# Power_Supply.net
KiCad netlist of a schematic drawn in Altium Designer
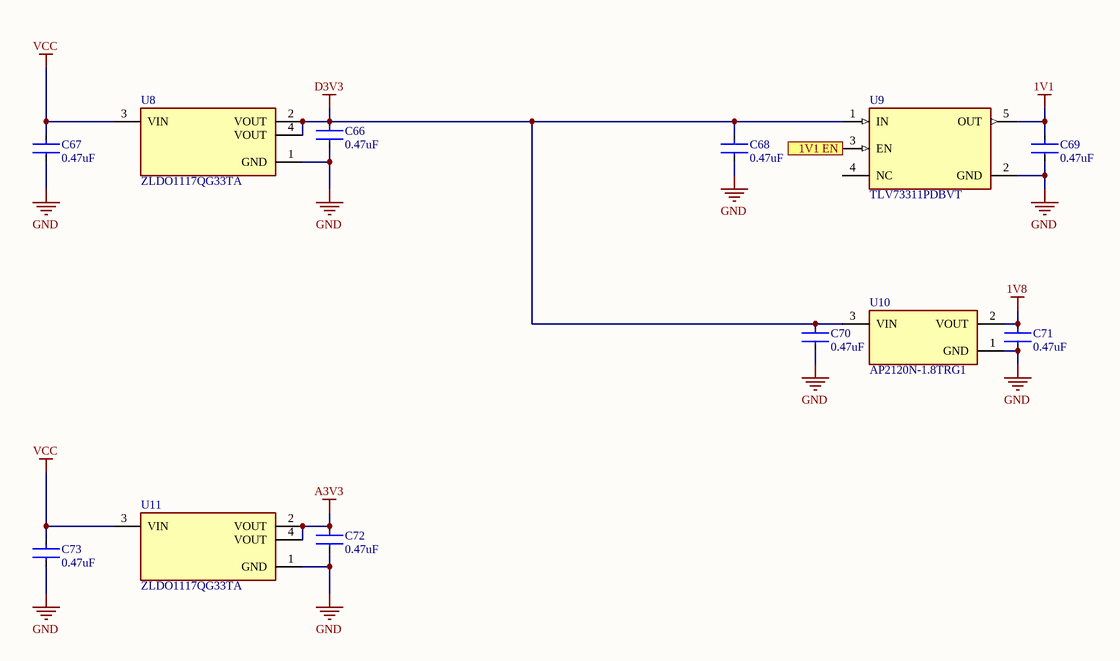
[diagram p0: Power Supply.SchDoc]

(export (version "E")
  (design (tool "Eeschema 10.0.6"))
  (components
    (comp (ref "C66")
      (value "0.47uF")
      (footprint "FP-GRM15-MFG")
      (description "CAP CER 0.1UF 16V X7R 0402")
      (fields (field (name "MANUFACTURER PART NUMBER") "GRM155R71C104KA88D") (field (name "TOLERANCE") "10%"))
      (libsource (lib "Altium Content Vault") (part "236180d848d6139a670b325ea6854c9"))
    )
    (comp (ref "C67")
      (value "0.47uF")
      (footprint "FP-GRM15-MFG")
      (description "CAP CER 0.1UF 16V X7R 0402")
      (fields (field (name "MANUFACTURER PART NUMBER") "GRM155R71C104KA88D") (field (name "TOLERANCE") "10%"))
      (libsource (lib "Altium Content Vault") (part "236180d848d6139a670b325ea6854c9"))
    )
    (comp (ref "C68")
      (value "0.47uF")
      (footprint "FP-GRM15-MFG")
      (description "CAP CER 0.1UF 16V X7R 0402")
      (fields (field (name "MANUFACTURER PART NUMBER") "GRM155R71C104KA88D") (field (name "TOLERANCE") "10%"))
      (libsource (lib "Altium Content Vault") (part "236180d848d6139a670b325ea6854c9"))
    )
    (comp (ref "C69")
      (value "0.47uF")
      (footprint "FP-GRM15-MFG")
      (description "CAP CER 0.1UF 16V X7R 0402")
      (fields (field (name "MANUFACTURER PART NUMBER") "GRM155R71C104KA88D") (field (name "TOLERANCE") "10%"))
      (libsource (lib "Altium Content Vault") (part "236180d848d6139a670b325ea6854c9"))
    )
    (comp (ref "C70")
      (value "0.47uF")
      (footprint "FP-GRM15-MFG")
      (description "CAP CER 0.1UF 16V X7R 0402")
      (fields (field (name "MANUFACTURER PART NUMBER") "GRM155R71C104KA88D") (field (name "TOLERANCE") "10%"))
      (libsource (lib "Altium Content Vault") (part "236180d848d6139a670b325ea6854c9"))
    )
    (comp (ref "C71")
      (value "0.47uF")
      (footprint "FP-GRM15-MFG")
      (description "CAP CER 0.1UF 16V X7R 0402")
      (fields (field (name "MANUFACTURER PART NUMBER") "GRM155R71C104KA88D") (field (name "TOLERANCE") "10%"))
      (libsource (lib "Altium Content Vault") (part "236180d848d6139a670b325ea6854c9"))
    )
    (comp (ref "C72")
      (value "0.47uF")
      (footprint "FP-GRM15-MFG")
      (description "CAP CER 0.1UF 16V X7R 0402")
      (fields (field (name "MANUFACTURER PART NUMBER") "GRM155R71C104KA88D") (field (name "TOLERANCE") "10%"))
      (libsource (lib "Altium Content Vault") (part "236180d848d6139a670b325ea6854c9"))
    )
    (comp (ref "C73")
      (value "0.47uF")
      (footprint "FP-GRM15-MFG")
      (description "CAP CER 0.1UF 16V X7R 0402")
      (fields (field (name "MANUFACTURER PART NUMBER") "GRM155R71C104KA88D") (field (name "TOLERANCE") "10%"))
      (libsource (lib "Altium Content Vault") (part "236180d848d6139a670b325ea6854c9"))
    )
    (comp (ref "U8")
      (value "ZLDO1117QG33TA")
      (footprint "FP-SOT223-MFG")
      (description "IC REG LINEAR 3.3V 1A SOT223-3")
      (fields (field (name "TOLERANCE") "2%"))
      (libsource (lib "Altium Content Vault") (part "e8e3cda12977690329f4a6520c2f0b2"))
    )
    (comp (ref "U9")
      (value "TLV73311PDBVT")
      (footprint "FP-DBV0005A-IPC_C")
      (description "IC REG LINEAR 1.1V 300MA SOT23-5")
      (libsource (lib "Altium Content Vault") (part "4670bf8a164e1b8604192632250c220"))
    )
    (comp (ref "U10")
      (value "AP2120N-1.8TRG1")
      (footprint "FP-SOT23-IPC_A")
      (description "IC REG LINEAR 1.8V 150MA SOT23")
      (libsource (lib "Altium Content Vault") (part "99960f24aedc7394e144d1df79132fe"))
    )
    (comp (ref "U11")
      (value "ZLDO1117QG33TA")
      (footprint "FP-SOT223-MFG")
      (description "IC REG LINEAR 3.3V 1A SOT223-3")
      (fields (field (name "TOLERANCE") "2%"))
      (libsource (lib "Altium Content Vault") (part "e8e3cda12977690329f4a6520c2f0b2"))
    )
  )
  (nets
    (net (code "1") (name "/1V1 EN") (class "Default")
      (node (ref "U9") (pin "3") (pinfunction "EN_3") (pintype "input"))
    )
    (net (code "2") (name "1V1") (class "Default")
      (node (ref "C69") (pin "2") (pinfunction "2_2") (pintype "passive"))
      (node (ref "U9") (pin "5") (pinfunction "OUT_5") (pintype "output"))
    )
    (net (code "3") (name "1V8") (class "Default")
      (node (ref "C71") (pin "2") (pinfunction "2_2") (pintype "passive"))
      (node (ref "U10") (pin "2") (pinfunction "VOUT_2") (pintype "power_in"))
    )
    (net (code "4") (name "A3V3") (class "Default")
      (node (ref "C72") (pin "2") (pinfunction "2_2") (pintype "passive"))
      (node (ref "U11") (pin "2") (pinfunction "VOUT_2") (pintype "power_in"))
      (node (ref "U11") (pin "4") (pinfunction "VOUT_4") (pintype "power_in"))
    )
    (net (code "5") (name "D3V3") (class "Default")
      (node (ref "C66") (pin "2") (pinfunction "2_2") (pintype "passive"))
      (node (ref "C68") (pin "2") (pinfunction "2_2") (pintype "passive"))
      (node (ref "C70") (pin "2") (pinfunction "2_2") (pintype "passive"))
      (node (ref "U10") (pin "3") (pinfunction "VIN_3") (pintype "power_in"))
      (node (ref "U8") (pin "2") (pinfunction "VOUT_2") (pintype "power_in"))
      (node (ref "U8") (pin "4") (pinfunction "VOUT_4") (pintype "power_in"))
      (node (ref "U9") (pin "1") (pinfunction "IN_1") (pintype "input"))
    )
    (net (code "6") (name "GND") (class "Default")
      (node (ref "C66") (pin "1") (pinfunction "1_1") (pintype "passive"))
      (node (ref "C67") (pin "1") (pinfunction "1_1") (pintype "passive"))
      (node (ref "C68") (pin "1") (pinfunction "1_1") (pintype "passive"))
      (node (ref "C69") (pin "1") (pinfunction "1_1") (pintype "passive"))
      (node (ref "C70") (pin "1") (pinfunction "1_1") (pintype "passive"))
      (node (ref "C71") (pin "1") (pinfunction "1_1") (pintype "passive"))
      (node (ref "C72") (pin "1") (pinfunction "1_1") (pintype "passive"))
      (node (ref "C73") (pin "1") (pinfunction "1_1") (pintype "passive"))
      (node (ref "U10") (pin "1") (pinfunction "GND_1") (pintype "power_in"))
      (node (ref "U11") (pin "1") (pinfunction "GND_1") (pintype "power_in"))
      (node (ref "U8") (pin "1") (pinfunction "GND_1") (pintype "power_in"))
      (node (ref "U9") (pin "2") (pinfunction "GND_2") (pintype "power_in"))
    )
    (net (code "7") (name "VCC") (class "Default")
      (node (ref "C67") (pin "2") (pinfunction "2_2") (pintype "passive"))
      (node (ref "C73") (pin "2") (pinfunction "2_2") (pintype "passive"))
      (node (ref "U11") (pin "3") (pinfunction "VIN_3") (pintype "power_in"))
      (node (ref "U8") (pin "3") (pinfunction "VIN_3") (pintype "power_in"))
    )
    (net (code "8") (name "unconnected-(U9-NC-Pad4)") (class "Default")
      (node (ref "U9") (pin "4") (pinfunction "NC_4") (pintype "passive"))
    )
  )
)
